# Aptomat_buttons_and_leds.net
KiCad netlist of a schematic drawn in Altium Designer
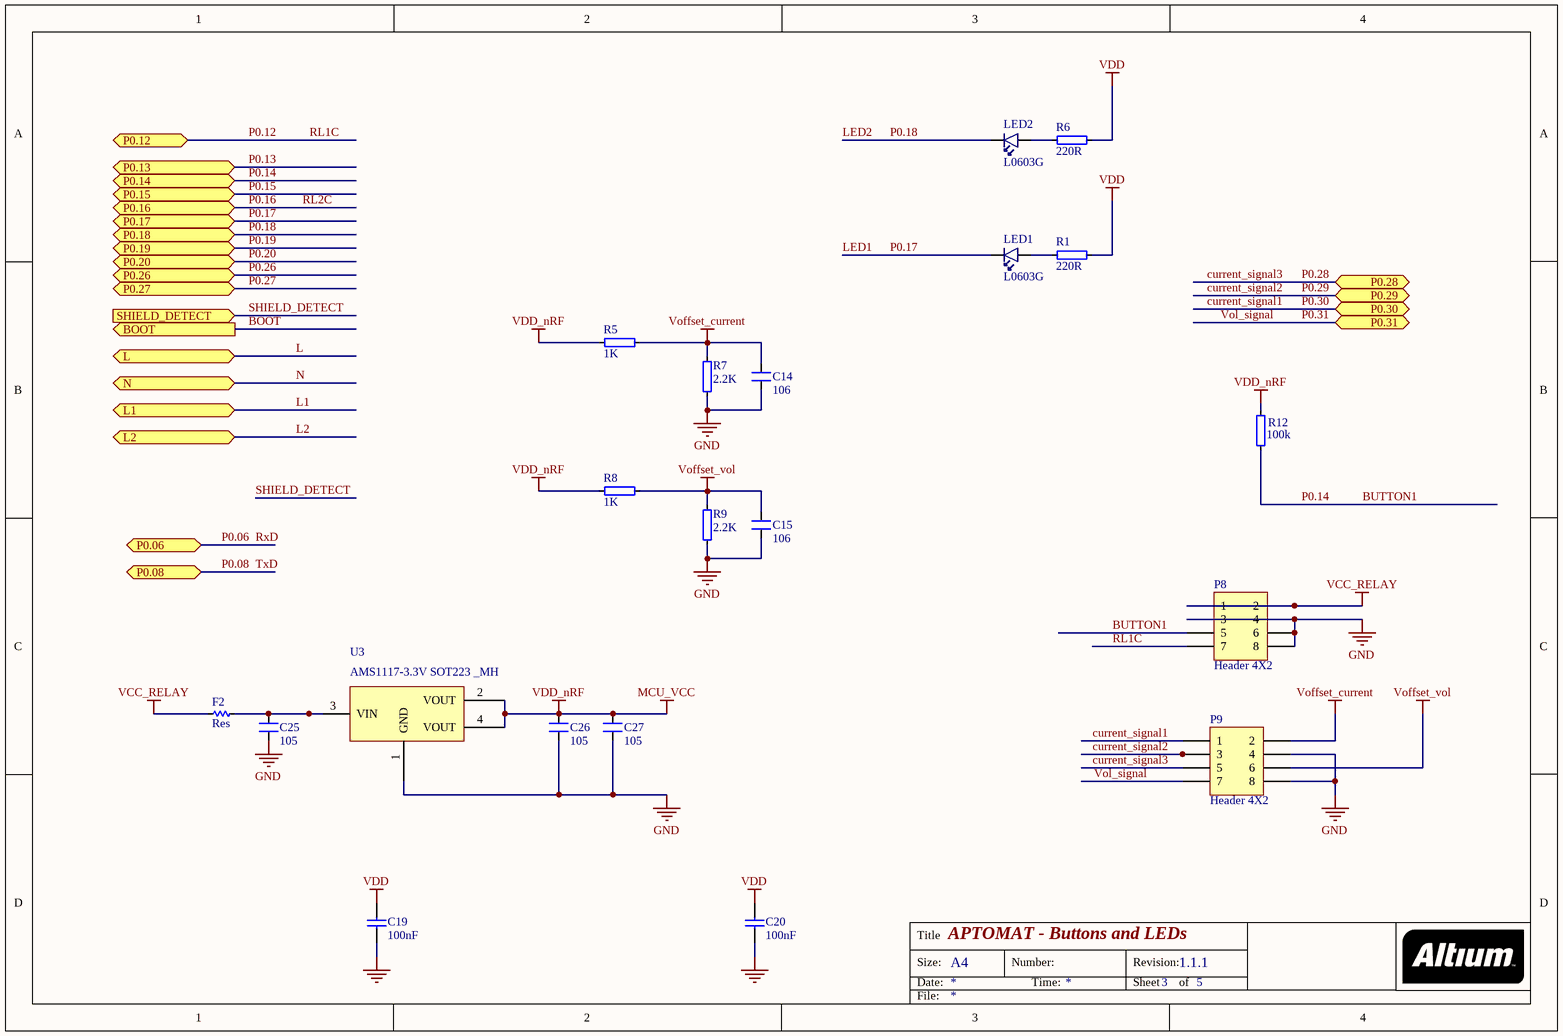
[diagram p0: Aptomat_buttons_and_leds.SchDoc]

(export (version "E")
  (design (tool "Eeschema 10.0.6"))
  (components
    (comp (ref "C14")
      (value "106")
      (footprint "0805_HV")
      (description "Cap SMD")
      (libsource (lib "hatcatbietbay") (part "CM"))
    )
    (comp (ref "C15")
      (value "106")
      (footprint "0805_HV")
      (description "Cap SMD")
      (libsource (lib "hatcatbietbay") (part "CM"))
    )
    (comp (ref "C19")
      (value "100nF")
      (footprint "CAPC1005X04L")
      (description "Capacitor, X7R, ±10%")
      (fields (field (name "PART NUMBER") "C0402-100n") (field (name "PUBLISHER") "Nordic Semiconductor"))
      (libsource (lib "Nordic Passive DB") (part "CAP"))
    )
    (comp (ref "C20")
      (value "100nF")
      (footprint "CAPC1005X04L")
      (description "Capacitor, X7R, ±10%")
      (fields (field (name "PART NUMBER") "C0402-100n") (field (name "PUBLISHER") "Nordic Semiconductor"))
      (libsource (lib "Nordic Passive DB") (part "CAP"))
    )
    (comp (ref "C25")
      (value "105")
      (footprint "0805_HV")
      (description "Cap SMD")
      (libsource (lib "hatcatbietbay") (part "CM"))
    )
    (comp (ref "C26")
      (value "105")
      (footprint "0805_HV")
      (description "Cap SMD")
      (libsource (lib "hatcatbietbay") (part "CM"))
    )
    (comp (ref "C27")
      (value "105")
      (footprint "0805_HV")
      (description "Cap SMD")
      (libsource (lib "hatcatbietbay") (part "CM"))
    )
    (comp (ref "F2")
      (value "Res")
      (footprint "1206")
      (description "Resistor")
      (fields
        (field (name "MANUFACTURER") "Generic Components")
        (field (name "PUBLISHER") "Altium Hobart Technology Centre")
      )
      (libsource (lib "LIBRARY") (part "Res-SMD"))
    )
    (comp (ref "LED1")
      (value "L0603G")
      (footprint "LED_0603_G")
      (description "LED SMARTLED GREEN 570NM 0603")
      (fields
        (field (name "PART NUMBER") "LG L29K Smartled Green")
        (field (name "MANUFACTURER") "Multicomp")
        (field (name "PUBLISHER") "Nordic Semiconductor")
      )
      (libsource (lib "Nordic Discrete DB") (part "D{colon}LED"))
    )
    (comp (ref "LED2")
      (value "L0603G")
      (footprint "LED_0603_G")
      (description "LED SMARTLED GREEN 570NM 0603")
      (fields
        (field (name "PART NUMBER") "LG L29K Smartled Green")
        (field (name "MANUFACTURER") "Multicomp")
        (field (name "PUBLISHER") "Nordic Semiconductor")
      )
      (libsource (lib "Nordic Discrete DB") (part "D{colon}LED"))
    )
    (comp (ref "P8")
      (value "Header 4X2")
      (footprint "HDR2X4")
      (description "Header, 4-Pin, Dual row")
      (fields (field (name "PUBLISHER") "Altium Limited"))
      (libsource (lib "Miscellaneous Connectors") (part "Header 4X2"))
    )
    (comp (ref "P9")
      (value "Header 4X2")
      (footprint "HDR2X4")
      (description "Header, 4-Pin, Dual row")
      (fields (field (name "PUBLISHER") "Altium Limited"))
      (libsource (lib "Miscellaneous Connectors") (part "Header 4X2"))
    )
    (comp (ref "R1")
      (value "220R")
      (footprint "0603")
      (description "Resistor, ±1%, 0.063W")
      (fields (field (name "PART NUMBER") "R0402-220") (field (name "PUBLISHER") "Nordic Semiconductor"))
      (libsource (lib "Nordic Passive DB") (part "RES_1"))
    )
    (comp (ref "R5")
      (value "1K")
      (footprint "0805_HV")
      (description "Resistor, ±1%, 0.063W")
      (fields (field (name "PART NUMBER") "R0402-100k") (field (name "PUBLISHER") "Nordic Semiconductor"))
      (libsource (lib "Nordic Passive DB") (part "RES_1"))
    )
    (comp (ref "R6")
      (value "220R")
      (footprint "0603")
      (description "Resistor, ±1%, 0.063W")
      (fields (field (name "PART NUMBER") "R0402-220") (field (name "PUBLISHER") "Nordic Semiconductor"))
      (libsource (lib "Nordic Passive DB") (part "RES_1"))
    )
    (comp (ref "R7")
      (value "2.2K")
      (footprint "0805_HV")
      (description "Resistor, ±1%, 0.063W")
      (fields (field (name "PART NUMBER") "R0402-100k") (field (name "PUBLISHER") "Nordic Semiconductor"))
      (libsource (lib "Nordic Passive DB") (part "RES_1"))
    )
    (comp (ref "R8")
      (value "1K")
      (footprint "0805_HV")
      (description "Resistor, ±1%, 0.063W")
      (fields (field (name "PART NUMBER") "R0402-100k") (field (name "PUBLISHER") "Nordic Semiconductor"))
      (libsource (lib "Nordic Passive DB") (part "RES_1"))
    )
    (comp (ref "R9")
      (value "2.2K")
      (footprint "0805_HV")
      (description "Resistor, ±1%, 0.063W")
      (fields (field (name "PART NUMBER") "R0402-100k") (field (name "PUBLISHER") "Nordic Semiconductor"))
      (libsource (lib "Nordic Passive DB") (part "RES_1"))
    )
    (comp (ref "R12")
      (value "100k")
      (footprint "0603")
      (description "Resistor, ±1%, 0.063W")
      (fields (field (name "PART NUMBER") "R0402-100k") (field (name "PUBLISHER") "Nordic Semiconductor"))
      (libsource (lib "Nordic Passive DB") (part "RES_1"))
    )
    (comp (ref "U3")
      (value "AMS1117-3.3V SOT223 _MH")
      (footprint "SOT223")
      (libsource (lib "MH_DA_THU_VIEN_16122016") (part "AMS1117-3.3V SOT223 _MH"))
    )
  )
  (nets
    (net (code "2") (name "/BUTTON1") (class "Default")
      (node (ref "P8") (pin "5") (pinfunction "5_5") (pintype "passive"))
      (node (ref "R12") (pin "1") (pinfunction "1_1") (pintype "passive"))
    )
    (net (code "6") (name "/LED1") (class "Default")
      (node (ref "LED1") (pin "1") (pinfunction "C_1") (pintype "passive"))
    )
    (net (code "7") (name "/LED2") (class "Default")
      (node (ref "LED2") (pin "1") (pinfunction "C_1") (pintype "passive"))
    )
    (net (code "11") (name "/P0.12") (class "Default")
      (node (ref "P8") (pin "7") (pinfunction "7_7") (pintype "passive"))
    )
    (net (code "19") (name "/P0.28") (class "Default")
      (node (ref "P9") (pin "5") (pinfunction "5_5") (pintype "passive"))
    )
    (net (code "20") (name "/P0.29") (class "Default")
      (node (ref "P9") (pin "3") (pinfunction "3_3") (pintype "passive"))
    )
    (net (code "21") (name "/P0.30") (class "Default")
      (node (ref "P9") (pin "1") (pinfunction "1_1") (pintype "passive"))
    )
    (net (code "22") (name "/P0.31") (class "Default")
      (node (ref "P9") (pin "7") (pinfunction "7_7") (pintype "passive"))
    )
    (net (code "24") (name "GND") (class "Default")
      (node (ref "C14") (pin "1") (pinfunction "1_1") (pintype "passive"))
      (node (ref "C15") (pin "1") (pinfunction "1_1") (pintype "passive"))
      (node (ref "C19") (pin "1") (pinfunction "1_1") (pintype "passive"))
      (node (ref "C20") (pin "1") (pinfunction "1_1") (pintype "passive"))
      (node (ref "C25") (pin "1") (pinfunction "1_1") (pintype "passive"))
      (node (ref "C26") (pin "1") (pinfunction "1_1") (pintype "passive"))
      (node (ref "C27") (pin "1") (pinfunction "1_1") (pintype "passive"))
      (node (ref "P8") (pin "3") (pinfunction "3_3") (pintype "passive"))
      (node (ref "P8") (pin "4") (pinfunction "4_4") (pintype "passive"))
      (node (ref "P8") (pin "6") (pinfunction "6_6") (pintype "passive"))
      (node (ref "P8") (pin "8") (pinfunction "8_8") (pintype "passive"))
      (node (ref "P9") (pin "4") (pinfunction "4_4") (pintype "passive"))
      (node (ref "P9") (pin "8") (pinfunction "8_8") (pintype "passive"))
      (node (ref "R7") (pin "2") (pinfunction "2_2") (pintype "passive"))
      (node (ref "R9") (pin "2") (pinfunction "2_2") (pintype "passive"))
      (node (ref "U3") (pin "1") (pinfunction "GND_1") (pintype "passive"))
    )
    (net (code "25") (name "MCU_VCC") (class "Default")
      (node (ref "C26") (pin "2") (pinfunction "2_2") (pintype "passive"))
      (node (ref "C27") (pin "2") (pinfunction "2_2") (pintype "passive"))
      (node (ref "R12") (pin "2") (pinfunction "2_2") (pintype "passive"))
      (node (ref "R5") (pin "2") (pinfunction "2_2") (pintype "passive"))
      (node (ref "R8") (pin "2") (pinfunction "2_2") (pintype "passive"))
      (node (ref "U3") (pin "2") (pinfunction "VOUT_2") (pintype "passive"))
      (node (ref "U3") (pin "4") (pinfunction "VOUT_4") (pintype "passive"))
    )
    (net (code "26") (name "Net-(LED1-A)") (class "Default")
      (node (ref "LED1") (pin "2") (pinfunction "A_2") (pintype "passive"))
      (node (ref "R1") (pin "1") (pinfunction "1_1") (pintype "passive"))
    )
    (net (code "27") (name "Net-(LED2-A)") (class "Default")
      (node (ref "LED2") (pin "2") (pinfunction "A_2") (pintype "passive"))
      (node (ref "R6") (pin "1") (pinfunction "1_1") (pintype "passive"))
    )
    (net (code "28") (name "Net-(U3-VIN)") (class "Default")
      (node (ref "C25") (pin "2") (pinfunction "2_2") (pintype "passive"))
      (node (ref "F2") (pin "1") (pinfunction "1_1") (pintype "passive"))
      (node (ref "U3") (pin "3") (pinfunction "VIN_3") (pintype "passive"))
    )
    (net (code "29") (name "VCC_RELAY") (class "Default")
      (node (ref "F2") (pin "2") (pinfunction "2_2") (pintype "passive"))
      (node (ref "P8") (pin "1") (pinfunction "1_1") (pintype "passive"))
      (node (ref "P8") (pin "2") (pinfunction "2_2") (pintype "passive"))
    )
    (net (code "30") (name "VDD") (class "Default")
      (node (ref "C19") (pin "2") (pinfunction "2_2") (pintype "passive"))
      (node (ref "C20") (pin "2") (pinfunction "2_2") (pintype "passive"))
      (node (ref "R1") (pin "2") (pinfunction "2_2") (pintype "passive"))
      (node (ref "R6") (pin "2") (pinfunction "2_2") (pintype "passive"))
    )
    (net (code "31") (name "Voffset_current") (class "Default")
      (node (ref "C14") (pin "2") (pinfunction "2_2") (pintype "passive"))
      (node (ref "P9") (pin "2") (pinfunction "2_2") (pintype "passive"))
      (node (ref "R5") (pin "1") (pinfunction "1_1") (pintype "passive"))
      (node (ref "R7") (pin "1") (pinfunction "1_1") (pintype "passive"))
    )
    (net (code "32") (name "Voffset_vol") (class "Default")
      (node (ref "C15") (pin "2") (pinfunction "2_2") (pintype "passive"))
      (node (ref "P9") (pin "6") (pinfunction "6_6") (pintype "passive"))
      (node (ref "R8") (pin "1") (pinfunction "1_1") (pintype "passive"))
      (node (ref "R9") (pin "1") (pinfunction "1_1") (pintype "passive"))
    )
  )
)
